# led.net
KiCad netlist of a schematic drawn in Altium Designer
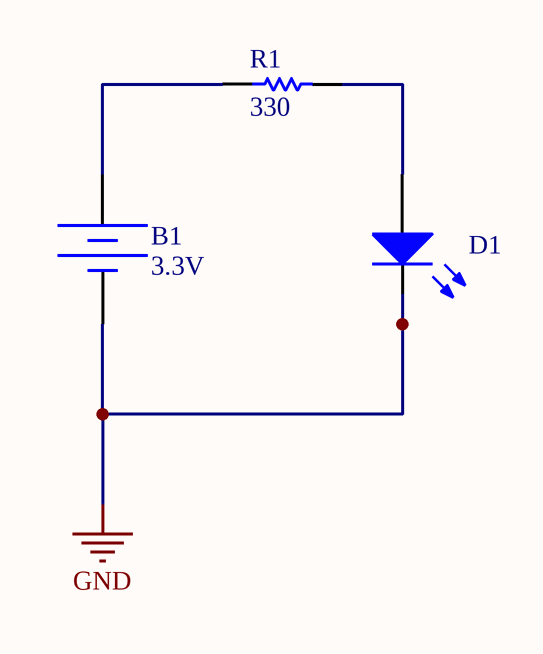
[diagram p0: led.SchDoc]

(export (version "E")
  (design (tool "Eeschema 10.0.6"))
  (components
    (comp (ref "B1")
      (value "Constant Voltage Source")
      (fields (field (name "DC MAGNITUDE") "3.3V"))
      (libsource (lib "Simulation Generic Components") (part "Battery"))
    )
    (comp (ref "D1")
      (value "Light-Emitting Diode")
      (libsource (lib "Simulation Generic Components") (part "LED"))
    )
    (comp (ref "R1")
      (value "330")
      (description "Resistor")
      (libsource (lib "Simulation Generic Components") (part "Resistor"))
    )
  )
  (nets
    (net (code "1") (name "GND") (class "Default")
      (node (ref "B1") (pin "2") (pinfunction "2_2") (pintype "passive"))
      (node (ref "D1") (pin "2") (pinfunction "K_2") (pintype "passive"))
    )
    (net (code "2") (name "Net-(B1-Pad1)") (class "Default")
      (node (ref "B1") (pin "1") (pinfunction "1_1") (pintype "passive"))
      (node (ref "R1") (pin "1") (pinfunction "1_1") (pintype "passive"))
    )
    (net (code "3") (name "Net-(D1-A)") (class "Default")
      (node (ref "D1") (pin "1") (pinfunction "A_1") (pintype "passive"))
      (node (ref "R1") (pin "2") (pinfunction "2_2") (pintype "passive"))
    )
  )
)
